# STM32_BareBones.net
KiCad netlist of a schematic drawn in Altium Designer
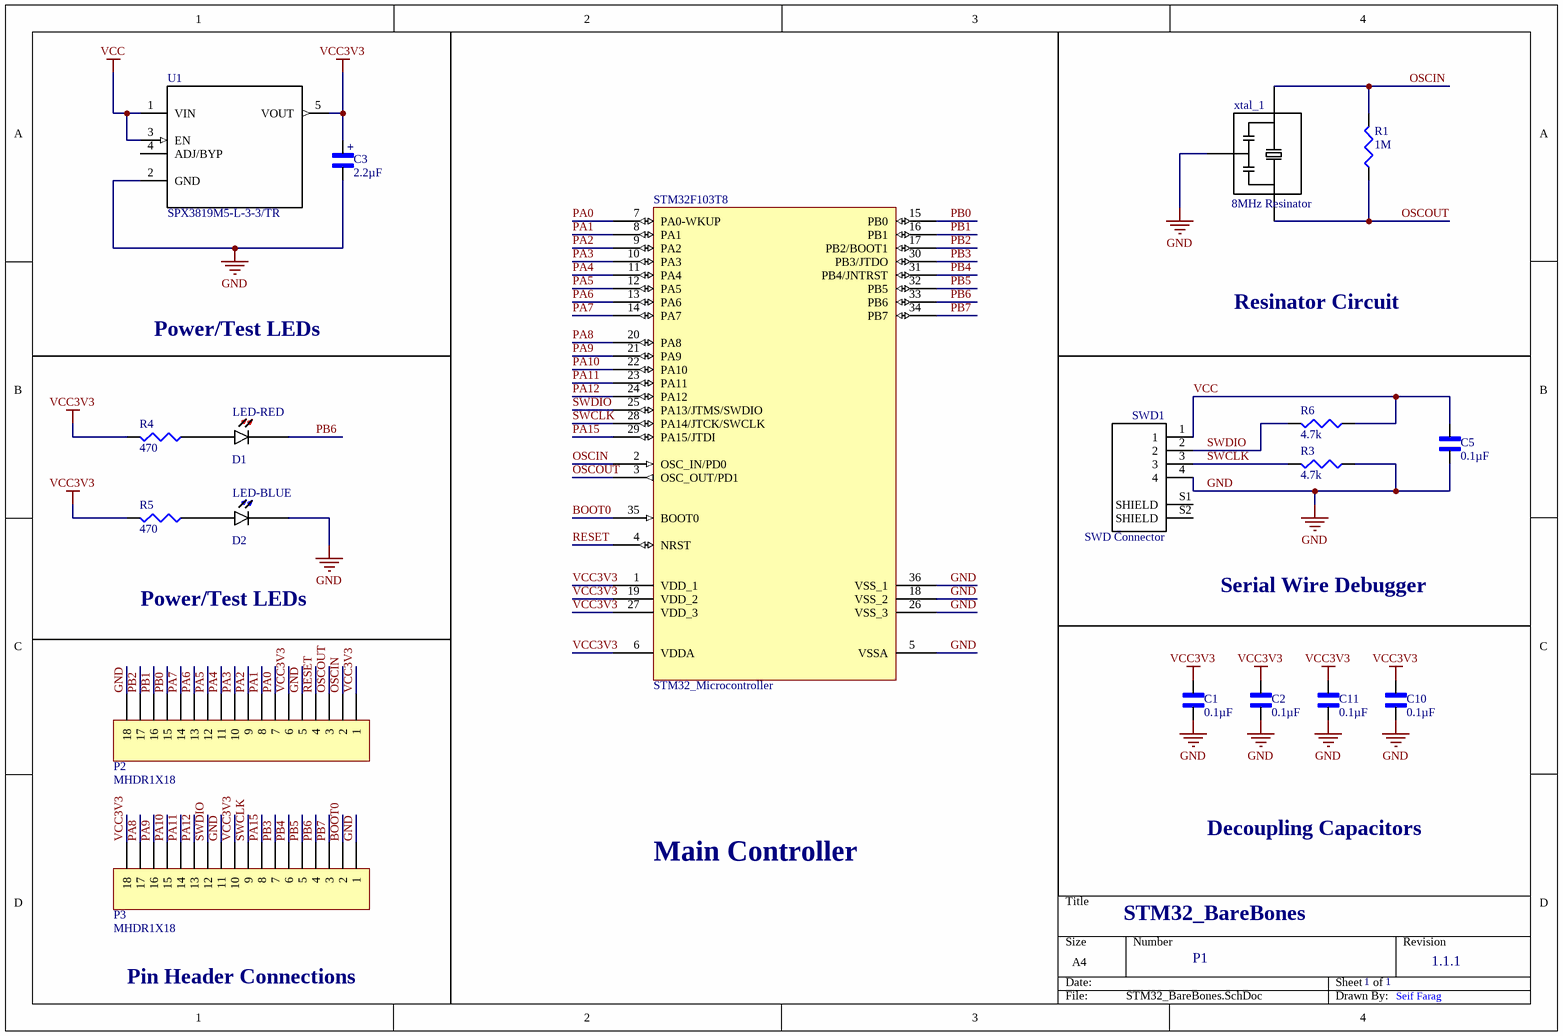
[diagram p0: STM32_BareBones.SchDoc]

(export (version "E")
  (design (tool "Eeschema 10.0.6"))
  (components
    (comp (ref "C1")
      (value "0.1µF")
      (footprint "CAPC1608X90N")
      (description "0.47µF ±10% 50V Ceramic Capacitor X7R 0603 _1608 Metric_")
      (fields (field (name "MF") "TDK") (field (name "MP") "C1608X7R1H474K080AC"))
      (libsource (lib "lib") (part "C1608X7R1H474K080AC"))
    )
    (comp (ref "C2")
      (value "0.1µF")
      (footprint "CAPC1608X90N")
      (description "0.47µF ±10% 50V Ceramic Capacitor X7R 0603 _1608 Metric_")
      (fields (field (name "MF") "TDK") (field (name "MP") "C1608X7R1H474K080AC"))
      (libsource (lib "lib") (part "C1608X7R1H474K080AC"))
    )
    (comp (ref "C3")
      (value "2.2µF")
      (footprint "CAPC1608X90N")
      (description "0.47µF ±10% 50V Ceramic Capacitor X7R 0603 _1608 Metric_")
      (fields (field (name "MF") "TDK") (field (name "MP") "C1608X7R1H474K080AC"))
      (libsource (lib "lib") (part "C1608X7R1H474K080AC"))
    )
    (comp (ref "C5")
      (value "0.1µF")
      (footprint "CAPC1608X90N")
      (description "0.47µF ±10% 50V Ceramic Capacitor X7R 0603 _1608 Metric_")
      (fields (field (name "MF") "TDK") (field (name "MP") "C1608X7R1H474K080AC"))
      (libsource (lib "lib") (part "C1608X7R1H474K080AC"))
    )
    (comp (ref "C10")
      (value "0.1µF")
      (footprint "CAPC1608X90N")
      (description "0.47µF ±10% 50V Ceramic Capacitor X7R 0603 _1608 Metric_")
      (fields (field (name "MF") "TDK") (field (name "MP") "C1608X7R1H474K080AC"))
      (libsource (lib "") (part "C1608X7R1H474K080AC_1"))
    )
    (comp (ref "C11")
      (value "0.1µF")
      (footprint "CAPC1608X90N")
      (description "0.47µF ±10% 50V Ceramic Capacitor X7R 0603 _1608 Metric_")
      (fields (field (name "MF") "TDK") (field (name "MP") "C1608X7R1H474K080AC"))
      (libsource (lib "lib") (part "C1608X7R1H474K080AC"))
    )
    (comp (ref "D1")
      (value "LED-RED")
      (footprint "*LEDM1608X80_LTE-C1906R-14(Primary)")
      (description "Red 620nm LED Indication - Discrete 2.2V 0603 (1608 Metric)")
      (fields (field (name "MP") "LTST-C194KRKT or SML-D12U1WT86"))
      (libsource (lib "lib") (part "0603-LED-RED"))
    )
    (comp (ref "D2")
      (value "LED-BLUE")
      (footprint "*LEDM1608X80_LTE-C1906R-14(Primary)")
      (description "LED IrLED Chip LED 2-Pin SMD T/R")
      (fields (field (name "MP") "LTST-S270TBKT or  LTST-C194TBKT or LTST-C191TBKT or  SML-D12D1WT86"))
      (libsource (lib "lib") (part "0603-LED-BLUE"))
    )
    (comp (ref "P2")
      (value "MHDR1X18")
      (footprint "MHDR1X18")
      (description "Header, 18-Pin")
      (fields (field (name "PUBLISHER") "Altium Limited"))
      (libsource (lib "Miscellaneous Connectors") (part "MHDR1X18"))
    )
    (comp (ref "P3")
      (value "MHDR1X18")
      (footprint "MHDR1X18")
      (description "Header, 18-Pin")
      (fields (field (name "PUBLISHER") "Altium Limited"))
      (libsource (lib "Miscellaneous Connectors") (part "MHDR1X18"))
    )
    (comp (ref "R1")
      (value "1M")
      (footprint "J1-0603")
      (description "1 kOhms ±1% 0.1W, 1/10W Chip Resistor 0603 (1608 Metric) Moisture Resistant Thick Film")
      (fields (field (name "MF") "Yageo or NXP") (field (name "MP") "RC0603FR-101KL"))
      (libsource (lib "lib") (part "RC0603FR-101KL"))
    )
    (comp (ref "R3")
      (value "4.7k")
      (footprint "J1-0603")
      (description "1 kOhms ±1% 0.1W, 1/10W Chip Resistor 0603 (1608 Metric) Moisture Resistant Thick Film")
      (fields (field (name "MF") "Yageo or NXP") (field (name "MP") "RC0603FR-101KL"))
      (libsource (lib "lib") (part "RC0603FR-101KL"))
    )
    (comp (ref "R4")
      (value "470")
      (footprint "J1-0603")
      (description "1 kOhms ±1% 0.1W, 1/10W Chip Resistor 0603 (1608 Metric) Moisture Resistant Thick Film")
      (fields (field (name "MF") "Yageo or NXP") (field (name "MP") "RC0603FR-101KL"))
      (libsource (lib "lib") (part "RC0603FR-101KL"))
    )
    (comp (ref "R5")
      (value "470")
      (footprint "J1-0603")
      (description "1 kOhms ±1% 0.1W, 1/10W Chip Resistor 0603 (1608 Metric) Moisture Resistant Thick Film")
      (fields (field (name "MF") "Yageo or NXP") (field (name "MP") "RC0603FR-101KL"))
      (libsource (lib "lib") (part "RC0603FR-101KL"))
    )
    (comp (ref "R6")
      (value "4.7k")
      (footprint "J1-0603")
      (description "1 kOhms ±1% 0.1W, 1/10W Chip Resistor 0603 (1608 Metric) Moisture Resistant Thick Film")
      (fields (field (name "MF") "Yageo or NXP") (field (name "MP") "RC0603FR-101KL"))
      (libsource (lib "lib") (part "RC0603FR-101KL"))
    )
    (comp (ref "STM32F103T8")
      (value "STM32_Microcontroller")
      (footprint "*QFN50P600X600X100-37N")
      (description "STM32F103T8U6, Microcontroller 32BIT ARM 64K FLASH [VFQFPN-36]")
      (fields (field (name "MF") "STM") (field (name "MP") "STM32F103T8U6"))
      (libsource (lib "lib") (part "STM32F103T8"))
    )
    (comp (ref "SWD1")
      (value "SWD Connector")
      (footprint "JST_BM04B-GHS-holes")
      (description "Conn Shrouded Header HDR 4 POS 1.25mm Solder ST SMD Reel")
      (fields (field (name "MF") "JST Sales") (field (name "MP") "SM04B-GHS-TB(LF)(SN)"))
      (libsource (lib "lib") (part "SWD SM04B-GHS-TB(LF)(SN)-"))
    )
    (comp (ref "U1")
      (value "SPX3819M5-L-3-3/TR")
      (footprint "*SOT95P280X145-5N")
      (description "Low Dropout Voltage Regulator, Adjustable 0.5A, В±1%, 2.5 to 16 Vin, 5-Pin SOT-23")
      (fields (field (name "MF") "MaxLinear, Inc."))
      (libsource (lib "lib") (part "SPX3819M5-L-3-3/TR"))
    )
    (comp (ref "xtal_1")
      (value "8MHz Resinator")
      (footprint "*OSC_CSTCE8M00G55-R0")
      (description "Ceramic Resonator 8MHz ??0.5% _Tol_ ??0.2% _Stability_ 33pF 40Ohm 3-Pin CSMD T/R")
      (fields (field (name "MP") "CSTCE8M00G55-R0") (field (name "MF") "Murata"))
      (libsource (lib "lib") (part "CSTCE8M00G55-R0"))
    )
  )
  (nets
    (net (code "1") (name "/BOOT0") (class "Default")
      (node (ref "P3") (pin "2") (pinfunction "2_2") (pintype "passive"))
      (node (ref "STM32F103T8") (pin "35") (pinfunction "BOOT0_35") (pintype "input"))
    )
    (net (code "2") (name "/OSCIN") (class "Default")
      (node (ref "P2") (pin "2") (pinfunction "2_2") (pintype "passive"))
      (node (ref "R1") (pin "2") (pinfunction "2_2") (pintype "passive"))
      (node (ref "STM32F103T8") (pin "2") (pinfunction "OSC_IN/PD0_2") (pintype "input"))
      (node (ref "xtal_1") (pin "1") (pinfunction "1_1") (pintype "passive"))
    )
    (net (code "3") (name "/OSCOUT") (class "Default")
      (node (ref "P2") (pin "3") (pinfunction "3_3") (pintype "passive"))
      (node (ref "R1") (pin "1") (pinfunction "1_1") (pintype "passive"))
      (node (ref "STM32F103T8") (pin "3") (pinfunction "OSC_OUT/PD1_3") (pintype "output"))
      (node (ref "xtal_1") (pin "3") (pinfunction "3_3") (pintype "passive"))
    )
    (net (code "4") (name "/PA0") (class "Default")
      (node (ref "P2") (pin "7") (pinfunction "7_7") (pintype "passive"))
      (node (ref "STM32F103T8") (pin "7") (pinfunction "PA0-WKUP_7") (pintype "bidirectional"))
    )
    (net (code "5") (name "/PA1") (class "Default")
      (node (ref "P2") (pin "8") (pinfunction "8_8") (pintype "passive"))
      (node (ref "STM32F103T8") (pin "8") (pinfunction "PA1_8") (pintype "bidirectional"))
    )
    (net (code "6") (name "/PA2") (class "Default")
      (node (ref "P2") (pin "9") (pinfunction "9_9") (pintype "passive"))
      (node (ref "STM32F103T8") (pin "9") (pinfunction "PA2_9") (pintype "bidirectional"))
    )
    (net (code "7") (name "/PA3") (class "Default")
      (node (ref "P2") (pin "10") (pinfunction "10_10") (pintype "passive"))
      (node (ref "STM32F103T8") (pin "10") (pinfunction "PA3_10") (pintype "bidirectional"))
    )
    (net (code "8") (name "/PA4") (class "Default")
      (node (ref "P2") (pin "11") (pinfunction "11_11") (pintype "passive"))
      (node (ref "STM32F103T8") (pin "11") (pinfunction "PA4_11") (pintype "bidirectional"))
    )
    (net (code "9") (name "/PA5") (class "Default")
      (node (ref "P2") (pin "12") (pinfunction "12_12") (pintype "passive"))
      (node (ref "STM32F103T8") (pin "12") (pinfunction "PA5_12") (pintype "bidirectional"))
    )
    (net (code "10") (name "/PA6") (class "Default")
      (node (ref "P2") (pin "13") (pinfunction "13_13") (pintype "passive"))
      (node (ref "STM32F103T8") (pin "13") (pinfunction "PA6_13") (pintype "bidirectional"))
    )
    (net (code "11") (name "/PA7") (class "Default")
      (node (ref "P2") (pin "14") (pinfunction "14_14") (pintype "passive"))
      (node (ref "STM32F103T8") (pin "14") (pinfunction "PA7_14") (pintype "bidirectional"))
    )
    (net (code "12") (name "/PA8") (class "Default")
      (node (ref "P3") (pin "17") (pinfunction "17_17") (pintype "passive"))
      (node (ref "STM32F103T8") (pin "20") (pinfunction "PA8_20") (pintype "bidirectional"))
    )
    (net (code "13") (name "/PA9") (class "Default")
      (node (ref "P3") (pin "16") (pinfunction "16_16") (pintype "passive"))
      (node (ref "STM32F103T8") (pin "21") (pinfunction "PA9_21") (pintype "bidirectional"))
    )
    (net (code "14") (name "/PA10") (class "Default")
      (node (ref "P3") (pin "15") (pinfunction "15_15") (pintype "passive"))
      (node (ref "STM32F103T8") (pin "22") (pinfunction "PA10_22") (pintype "bidirectional"))
    )
    (net (code "15") (name "/PA11") (class "Default")
      (node (ref "P3") (pin "14") (pinfunction "14_14") (pintype "passive"))
      (node (ref "STM32F103T8") (pin "23") (pinfunction "PA11_23") (pintype "bidirectional"))
    )
    (net (code "16") (name "/PA12") (class "Default")
      (node (ref "P3") (pin "13") (pinfunction "13_13") (pintype "passive"))
      (node (ref "STM32F103T8") (pin "24") (pinfunction "PA12_24") (pintype "bidirectional"))
    )
    (net (code "17") (name "/PA15") (class "Default")
      (node (ref "P3") (pin "8") (pinfunction "8_8") (pintype "passive"))
      (node (ref "STM32F103T8") (pin "29") (pinfunction "PA15/JTDI_29") (pintype "bidirectional"))
    )
    (net (code "18") (name "/PB0") (class "Default")
      (node (ref "P2") (pin "15") (pinfunction "15_15") (pintype "passive"))
      (node (ref "STM32F103T8") (pin "15") (pinfunction "PB0_15") (pintype "bidirectional"))
    )
    (net (code "19") (name "/PB1") (class "Default")
      (node (ref "P2") (pin "16") (pinfunction "16_16") (pintype "passive"))
      (node (ref "STM32F103T8") (pin "16") (pinfunction "PB1_16") (pintype "bidirectional"))
    )
    (net (code "20") (name "/PB2") (class "Default")
      (node (ref "P2") (pin "17") (pinfunction "17_17") (pintype "passive"))
      (node (ref "STM32F103T8") (pin "17") (pinfunction "PB2/BOOT1_17") (pintype "bidirectional"))
    )
    (net (code "21") (name "/PB3") (class "Default")
      (node (ref "P3") (pin "7") (pinfunction "7_7") (pintype "passive"))
      (node (ref "STM32F103T8") (pin "30") (pinfunction "PB3/JTDO_30") (pintype "bidirectional"))
    )
    (net (code "22") (name "/PB4") (class "Default")
      (node (ref "P3") (pin "6") (pinfunction "6_6") (pintype "passive"))
      (node (ref "STM32F103T8") (pin "31") (pinfunction "PB4/JNTRST_31") (pintype "bidirectional"))
    )
    (net (code "23") (name "/PB5") (class "Default")
      (node (ref "P3") (pin "5") (pinfunction "5_5") (pintype "passive"))
      (node (ref "STM32F103T8") (pin "32") (pinfunction "PB5_32") (pintype "bidirectional"))
    )
    (net (code "24") (name "/PB6") (class "Default")
      (node (ref "D1") (pin "C") (pinfunction "C_C") (pintype "passive"))
      (node (ref "P3") (pin "4") (pinfunction "4_4") (pintype "passive"))
      (node (ref "STM32F103T8") (pin "33") (pinfunction "PB6_33") (pintype "bidirectional"))
    )
    (net (code "25") (name "/PB7") (class "Default")
      (node (ref "P3") (pin "3") (pinfunction "3_3") (pintype "passive"))
      (node (ref "STM32F103T8") (pin "34") (pinfunction "PB7_34") (pintype "bidirectional"))
    )
    (net (code "26") (name "/RESET") (class "Default")
      (node (ref "P2") (pin "4") (pinfunction "4_4") (pintype "passive"))
      (node (ref "STM32F103T8") (pin "4") (pinfunction "NRST_4") (pintype "bidirectional"))
    )
    (net (code "27") (name "/SWCLK") (class "Default")
      (node (ref "P3") (pin "9") (pinfunction "9_9") (pintype "passive"))
      (node (ref "R3") (pin "2") (pinfunction "2_2") (pintype "passive"))
      (node (ref "STM32F103T8") (pin "28") (pinfunction "PA14/JTCK/SWCLK_28") (pintype "bidirectional"))
      (node (ref "SWD1") (pin "3") (pinfunction "3_3") (pintype "passive"))
    )
    (net (code "28") (name "/SWDIO") (class "Default")
      (node (ref "P3") (pin "12") (pinfunction "12_12") (pintype "passive"))
      (node (ref "R6") (pin "2") (pinfunction "2_2") (pintype "passive"))
      (node (ref "STM32F103T8") (pin "25") (pinfunction "PA13/JTMS/SWDIO_25") (pintype "bidirectional"))
      (node (ref "SWD1") (pin "2") (pinfunction "2_2") (pintype "passive"))
    )
    (net (code "29") (name "GND") (class "Default")
      (node (ref "C1") (pin "1") (pinfunction "1_1") (pintype "passive"))
      (node (ref "C10") (pin "2") (pinfunction "2_2") (pintype "passive"))
      (node (ref "C11") (pin "1") (pinfunction "1_1") (pintype "passive"))
      (node (ref "C2") (pin "1") (pinfunction "1_1") (pintype "passive"))
      (node (ref "C3") (pin "1") (pinfunction "1_1") (pintype "passive"))
      (node (ref "C5") (pin "1") (pinfunction "1_1") (pintype "passive"))
      (node (ref "D2") (pin "C") (pinfunction "C_C") (pintype "passive"))
      (node (ref "P2") (pin "18") (pinfunction "18_18") (pintype "passive"))
      (node (ref "P2") (pin "5") (pinfunction "5_5") (pintype "passive"))
      (node (ref "P3") (pin "1") (pinfunction "1_1") (pintype "passive"))
      (node (ref "P3") (pin "11") (pinfunction "11_11") (pintype "passive"))
      (node (ref "R3") (pin "1") (pinfunction "1_1") (pintype "passive"))
      (node (ref "STM32F103T8") (pin "18") (pinfunction "VSS_2_18") (pintype "power_in"))
      (node (ref "STM32F103T8") (pin "26") (pinfunction "VSS_3_26") (pintype "power_in"))
      (node (ref "STM32F103T8") (pin "36") (pinfunction "VSS_1_36") (pintype "power_in"))
      (node (ref "STM32F103T8") (pin "5") (pinfunction "VSSA_5") (pintype "power_in"))
      (node (ref "SWD1") (pin "4") (pinfunction "4_4") (pintype "passive"))
      (node (ref "U1") (pin "2") (pinfunction "GND_2") (pintype "passive"))
      (node (ref "xtal_1") (pin "2") (pinfunction "2_2") (pintype "power_in"))
    )
    (net (code "30") (name "Net-(D1-PadA)") (class "Default")
      (node (ref "D1") (pin "A") (pinfunction "A_A") (pintype "passive"))
      (node (ref "R4") (pin "1") (pinfunction "1_1") (pintype "passive"))
    )
    (net (code "31") (name "Net-(D2-PadA)") (class "Default")
      (node (ref "D2") (pin "A") (pinfunction "A_A") (pintype "passive"))
      (node (ref "R5") (pin "1") (pinfunction "1_1") (pintype "passive"))
    )
    (net (code "32") (name "VCC") (class "Default")
      (node (ref "C5") (pin "2") (pinfunction "2_2") (pintype "passive"))
      (node (ref "R6") (pin "1") (pinfunction "1_1") (pintype "passive"))
      (node (ref "SWD1") (pin "1") (pinfunction "1_1") (pintype "passive"))
      (node (ref "U1") (pin "1") (pinfunction "VIN_1") (pintype "power_in"))
      (node (ref "U1") (pin "3") (pinfunction "EN_3") (pintype "input"))
    )
    (net (code "33") (name "VCC3V3") (class "Default")
      (node (ref "C1") (pin "2") (pinfunction "2_2") (pintype "passive"))
      (node (ref "C10") (pin "1") (pinfunction "1_1") (pintype "passive"))
      (node (ref "C11") (pin "2") (pinfunction "2_2") (pintype "passive"))
      (node (ref "C2") (pin "2") (pinfunction "2_2") (pintype "passive"))
      (node (ref "C3") (pin "2") (pinfunction "2_2") (pintype "passive"))
      (node (ref "P2") (pin "1") (pinfunction "1_1") (pintype "passive"))
      (node (ref "P2") (pin "6") (pinfunction "6_6") (pintype "passive"))
      (node (ref "P3") (pin "10") (pinfunction "10_10") (pintype "passive"))
      (node (ref "P3") (pin "18") (pinfunction "18_18") (pintype "passive"))
      (node (ref "R4") (pin "2") (pinfunction "2_2") (pintype "passive"))
      (node (ref "R5") (pin "2") (pinfunction "2_2") (pintype "passive"))
      (node (ref "STM32F103T8") (pin "1") (pinfunction "VDD_1_1") (pintype "power_in"))
      (node (ref "STM32F103T8") (pin "19") (pinfunction "VDD_2_19") (pintype "power_in"))
      (node (ref "STM32F103T8") (pin "27") (pinfunction "VDD_3_27") (pintype "power_in"))
      (node (ref "STM32F103T8") (pin "6") (pinfunction "VDDA_6") (pintype "power_in"))
      (node (ref "U1") (pin "5") (pinfunction "VOUT_5") (pintype "output"))
    )
    (net (code "34") (name "unconnected-(SWD1-SHIELD-PadS1)") (class "Default")
      (node (ref "SWD1") (pin "S1") (pinfunction "SHIELD_S1") (pintype "passive"))
    )
    (net (code "35") (name "unconnected-(SWD1-SHIELD-PadS2)") (class "Default")
      (node (ref "SWD1") (pin "S2") (pinfunction "SHIELD_S2") (pintype "passive"))
    )
    (net (code "36") (name "unconnected-(U1-ADJ{slash}BYP-Pad4)") (class "Default")
      (node (ref "U1") (pin "4") (pinfunction "ADJ/BYP_4") (pintype "passive"))
    )
  )
)
